# buoyancy-engine-connector-female.net
KiCad netlist of a schematic drawn in EAGLE
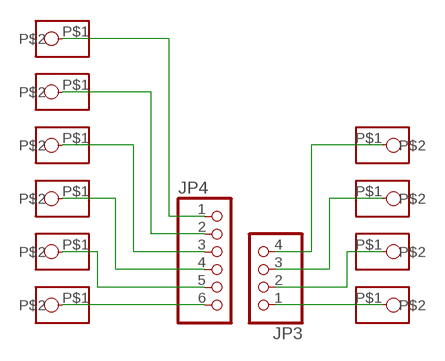
[diagram p0: schematic, sheet 1]

(export (version "E")
  (design (tool "Eeschema 10.0.6"))
  (components
    (comp (ref "JP3")
      (value "PINHD-1X4")
      (footprint "eagle-import:1X04")
      (libsource (lib "eagle-import") (part "PINHD-1X4"))
    )
    (comp (ref "JP4")
      (value "PINHD-1X6")
      (footprint "eagle-import:1X06")
      (libsource (lib "eagle-import") (part "PINHD-1X6"))
    )
    (comp (ref "U$1")
      (value "POGO-PIN-PAD")
      (footprint "eagle-import:POGO-PIN-PAD")
      (libsource (lib "eagle-import") (part "POGO-PIN-PAD"))
    )
    (comp (ref "U$2")
      (value "POGO-PIN-PAD")
      (footprint "eagle-import:POGO-PIN-PAD")
      (libsource (lib "eagle-import") (part "POGO-PIN-PAD"))
    )
    (comp (ref "U$3")
      (value "POGO-PIN-PAD")
      (footprint "eagle-import:POGO-PIN-PAD")
      (libsource (lib "eagle-import") (part "POGO-PIN-PAD"))
    )
    (comp (ref "U$4")
      (value "POGO-PIN-PAD")
      (footprint "eagle-import:POGO-PIN-PAD")
      (libsource (lib "eagle-import") (part "POGO-PIN-PAD"))
    )
    (comp (ref "U$5")
      (value "POGO-PIN-PAD")
      (footprint "eagle-import:POGO-PIN-PAD")
      (libsource (lib "eagle-import") (part "POGO-PIN-PAD"))
    )
    (comp (ref "U$6")
      (value "POGO-PIN-PAD")
      (footprint "eagle-import:POGO-PIN-PAD")
      (libsource (lib "eagle-import") (part "POGO-PIN-PAD"))
    )
    (comp (ref "U$7")
      (value "POGO-PIN-PAD")
      (footprint "eagle-import:POGO-PIN-PAD")
      (libsource (lib "eagle-import") (part "POGO-PIN-PAD"))
    )
    (comp (ref "U$8")
      (value "POGO-PIN-PAD")
      (footprint "eagle-import:POGO-PIN-PAD")
      (libsource (lib "eagle-import") (part "POGO-PIN-PAD"))
    )
    (comp (ref "U$9")
      (value "POGO-PIN-PAD")
      (footprint "eagle-import:POGO-PIN-PAD")
      (libsource (lib "eagle-import") (part "POGO-PIN-PAD"))
    )
    (comp (ref "U$10")
      (value "POGO-PIN-PAD")
      (footprint "eagle-import:POGO-PIN-PAD")
      (libsource (lib "eagle-import") (part "POGO-PIN-PAD"))
    )
  )
  (nets
    (net (code "1") (name "Net-(U$1-P$2)") (class "Default")
      (node (ref "JP4") (pin "6") (pinfunction "6_6") (pintype "passive"))
      (node (ref "U$1") (pin "P$1") (pinfunction "P$2_P$1") (pintype "bidirectional"))
    )
    (net (code "2") (name "Net-(U$2-P$2)") (class "Default")
      (node (ref "JP4") (pin "5") (pinfunction "5_5") (pintype "passive"))
      (node (ref "U$2") (pin "P$1") (pinfunction "P$2_P$1") (pintype "bidirectional"))
    )
    (net (code "3") (name "Net-(U$3-P$2)") (class "Default")
      (node (ref "JP4") (pin "4") (pinfunction "4_4") (pintype "passive"))
      (node (ref "U$3") (pin "P$1") (pinfunction "P$2_P$1") (pintype "bidirectional"))
    )
    (net (code "4") (name "Net-(U$4-P$2)") (class "Default")
      (node (ref "JP4") (pin "3") (pinfunction "3_3") (pintype "passive"))
      (node (ref "U$4") (pin "P$1") (pinfunction "P$2_P$1") (pintype "bidirectional"))
    )
    (net (code "5") (name "Net-(U$5-P$2)") (class "Default")
      (node (ref "JP4") (pin "2") (pinfunction "2_2") (pintype "passive"))
      (node (ref "U$5") (pin "P$1") (pinfunction "P$2_P$1") (pintype "bidirectional"))
    )
    (net (code "6") (name "Net-(U$6-P$2)") (class "Default")
      (node (ref "JP4") (pin "1") (pinfunction "1_1") (pintype "passive"))
      (node (ref "U$6") (pin "P$1") (pinfunction "P$2_P$1") (pintype "bidirectional"))
    )
    (net (code "7") (name "Net-(U$7-P$2)") (class "Default")
      (node (ref "JP3") (pin "3") (pinfunction "3_3") (pintype "passive"))
      (node (ref "U$7") (pin "P$1") (pinfunction "P$2_P$1") (pintype "bidirectional"))
    )
    (net (code "8") (name "Net-(U$8-P$2)") (class "Default")
      (node (ref "JP3") (pin "2") (pinfunction "2_2") (pintype "passive"))
      (node (ref "U$8") (pin "P$1") (pinfunction "P$2_P$1") (pintype "bidirectional"))
    )
    (net (code "9") (name "Net-(U$9-P$2)") (class "Default")
      (node (ref "JP3") (pin "1") (pinfunction "1_1") (pintype "passive"))
      (node (ref "U$9") (pin "P$1") (pinfunction "P$2_P$1") (pintype "bidirectional"))
    )
    (net (code "10") (name "Net-(U$10-P$2)") (class "Default")
      (node (ref "JP3") (pin "4") (pinfunction "4_4") (pintype "passive"))
      (node (ref "U$10") (pin "P$1") (pinfunction "P$2_P$1") (pintype "bidirectional"))
    )
  )
)
